# Filter.net
KiCad netlist of a schematic drawn in EAGLE
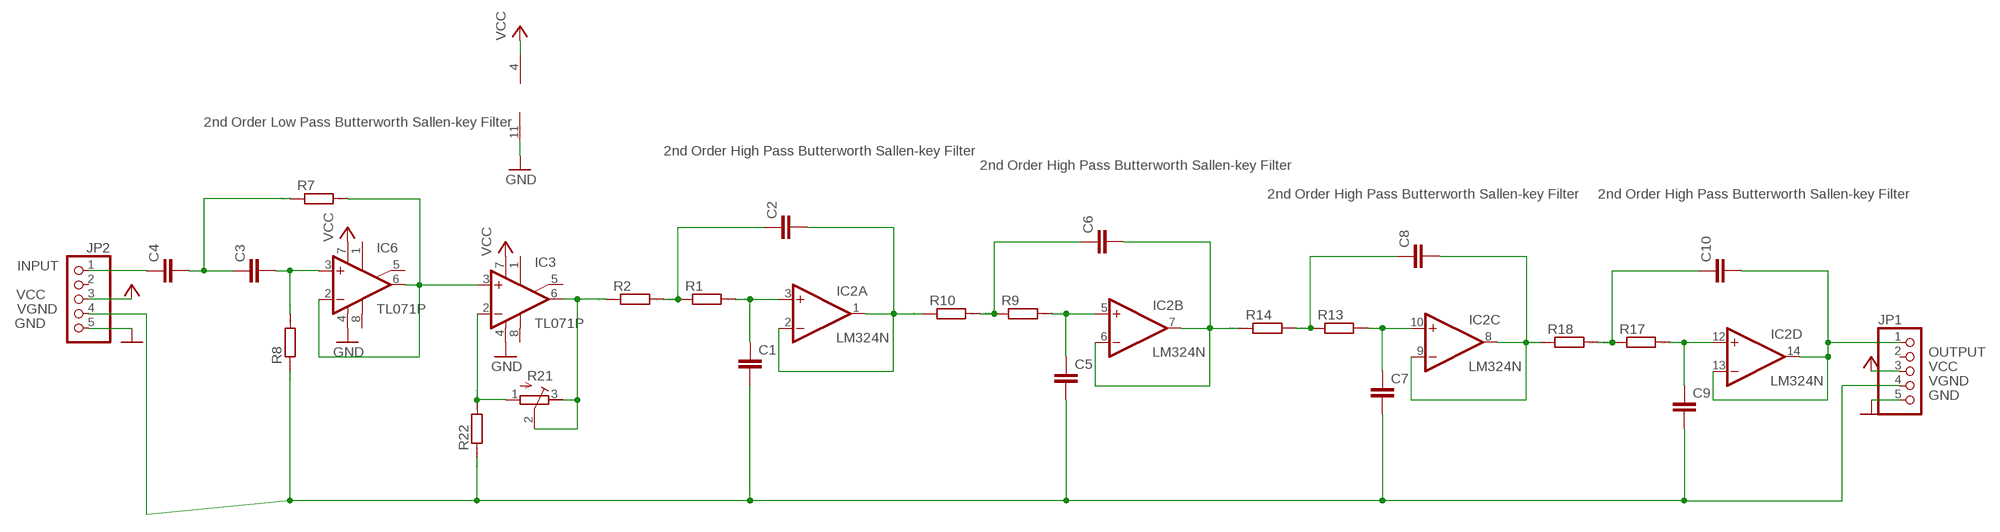
[diagram p0: schematic, sheet 1]

(export (version "E")
  (design (tool "Eeschema 10.0.6"))
  (components
    (comp (ref "C1")
      (value "C2.5/2")
      (footprint "eagle-import:C2.5-2")
      (libsource (lib "eagle-import") (part "C2.5/2"))
    )
    (comp (ref "C2")
      (value "C2.5/2")
      (footprint "eagle-import:C2.5-2")
      (libsource (lib "eagle-import") (part "C2.5/2"))
    )
    (comp (ref "C3")
      (value "C2.5/2")
      (footprint "eagle-import:C2.5-2")
      (libsource (lib "eagle-import") (part "C2.5/2"))
    )
    (comp (ref "C4")
      (value "C2.5/2")
      (footprint "eagle-import:C2.5-2")
      (libsource (lib "eagle-import") (part "C2.5/2"))
    )
    (comp (ref "C5")
      (value "C2.5/2")
      (footprint "eagle-import:C2.5-2")
      (libsource (lib "eagle-import") (part "C2.5/2"))
    )
    (comp (ref "C6")
      (value "C2.5/2")
      (footprint "eagle-import:C2.5-2")
      (libsource (lib "eagle-import") (part "C2.5/2"))
    )
    (comp (ref "C7")
      (value "C2.5/2")
      (footprint "eagle-import:C2.5-2")
      (libsource (lib "eagle-import") (part "C2.5/2"))
    )
    (comp (ref "C8")
      (value "C2.5/2")
      (footprint "eagle-import:C2.5-2")
      (libsource (lib "eagle-import") (part "C2.5/2"))
    )
    (comp (ref "C9")
      (value "C2.5/2")
      (footprint "eagle-import:C2.5-2")
      (libsource (lib "eagle-import") (part "C2.5/2"))
    )
    (comp (ref "C10")
      (value "C2.5/2")
      (footprint "eagle-import:C2.5-2")
      (libsource (lib "eagle-import") (part "C2.5/2"))
    )
    (comp (ref "IC2")
      (value "LM324N")
      (footprint "eagle-import:DIL14")
      (libsource (lib "eagle-import") (part "LM324N"))
    )
    (comp (ref "IC3")
      (value "TL071P")
      (footprint "eagle-import:DIL08")
      (libsource (lib "eagle-import") (part "TL071P"))
    )
    (comp (ref "IC6")
      (value "TL071P")
      (footprint "eagle-import:DIL08")
      (libsource (lib "eagle-import") (part "TL071P"))
    )
    (comp (ref "JP1")
      (value "PINHD-1X5")
      (footprint "eagle-import:1X05")
      (libsource (lib "eagle-import") (part "PINHD-1X5"))
    )
    (comp (ref "JP2")
      (value "PINHD-1X5")
      (footprint "eagle-import:1X05")
      (libsource (lib "eagle-import") (part "PINHD-1X5"))
    )
    (comp (ref "R1")
      (value "R0204/7")
      (footprint "eagle-import:0204_7")
      (libsource (lib "eagle-import") (part "R0204/7"))
    )
    (comp (ref "R2")
      (value "R0204/7")
      (footprint "eagle-import:0204_7")
      (libsource (lib "eagle-import") (part "R0204/7"))
    )
    (comp (ref "R7")
      (value "R0204/7")
      (footprint "eagle-import:0204_7")
      (libsource (lib "eagle-import") (part "R0204/7"))
    )
    (comp (ref "R8")
      (value "R0204/7")
      (footprint "eagle-import:0204_7")
      (libsource (lib "eagle-import") (part "R0204/7"))
    )
    (comp (ref "R9")
      (value "R0204/7")
      (footprint "eagle-import:0204_7")
      (libsource (lib "eagle-import") (part "R0204/7"))
    )
    (comp (ref "R10")
      (value "R0207/10")
      (footprint "eagle-import:0207_10")
      (libsource (lib "eagle-import") (part "R0207/10"))
    )
    (comp (ref "R13")
      (value "R0204/7")
      (footprint "eagle-import:0204_7")
      (libsource (lib "eagle-import") (part "R0204/7"))
    )
    (comp (ref "R14")
      (value "R0204/7")
      (footprint "eagle-import:0204_7")
      (libsource (lib "eagle-import") (part "R0204/7"))
    )
    (comp (ref "R17")
      (value "R0204/7")
      (footprint "eagle-import:0204_7")
      (libsource (lib "eagle-import") (part "R0204/7"))
    )
    (comp (ref "R18")
      (value "R0207/10")
      (footprint "eagle-import:0207_10")
      (libsource (lib "eagle-import") (part "R0207/10"))
    )
    (comp (ref "R21")
      (value "R-TRIMM3299W")
      (footprint "eagle-import:RTRIM3299W")
      (libsource (lib "eagle-import") (part "R-TRIMM3299W"))
    )
    (comp (ref "R22")
      (value "R0204/7")
      (footprint "eagle-import:0204_7")
      (libsource (lib "eagle-import") (part "R0204/7"))
    )
  )
  (nets
    (net (code "1") (name "/INPUT") (class "Default")
      (node (ref "C4") (pin "1") (pinfunction "1_1") (pintype "passive"))
      (node (ref "JP2") (pin "1") (pinfunction "1_1") (pintype "passive"))
    )
    (net (code "2") (name "/OUTPUT") (class "Default")
      (node (ref "C10") (pin "2") (pinfunction "2_2") (pintype "passive"))
      (node (ref "IC2") (pin "13") (pinfunction "-IN_13") (pintype "input"))
      (node (ref "IC2") (pin "14") (pinfunction "OUT_14") (pintype "output"))
      (node (ref "JP1") (pin "1") (pinfunction "1_1") (pintype "passive"))
    )
    (net (code "3") (name "/VGND") (class "Default")
      (node (ref "C1") (pin "2") (pinfunction "2_2") (pintype "passive"))
      (node (ref "C5") (pin "2") (pinfunction "2_2") (pintype "passive"))
      (node (ref "C7") (pin "2") (pinfunction "2_2") (pintype "passive"))
      (node (ref "C9") (pin "2") (pinfunction "2_2") (pintype "passive"))
      (node (ref "JP1") (pin "4") (pinfunction "4_4") (pintype "passive"))
      (node (ref "JP2") (pin "4") (pinfunction "4_4") (pintype "passive"))
      (node (ref "R22") (pin "1") (pinfunction "1_1") (pintype "passive"))
      (node (ref "R8") (pin "1") (pinfunction "1_1") (pintype "passive"))
    )
    (net (code "4") (name "GND") (class "Default")
      (node (ref "IC2") (pin "11") (pinfunction "V-_11") (pintype "power_in"))
      (node (ref "IC3") (pin "4") (pinfunction "V-_4") (pintype "power_in"))
      (node (ref "IC6") (pin "4") (pinfunction "V-_4") (pintype "power_in"))
      (node (ref "JP1") (pin "5") (pinfunction "5_5") (pintype "passive"))
      (node (ref "JP2") (pin "5") (pinfunction "5_5") (pintype "passive"))
    )
    (net (code "5") (name "Net-(C2-Pad1)") (class "Default")
      (node (ref "C2") (pin "1") (pinfunction "1_1") (pintype "passive"))
      (node (ref "R1") (pin "1") (pinfunction "1_1") (pintype "passive"))
      (node (ref "R2") (pin "2") (pinfunction "2_2") (pintype "passive"))
    )
    (net (code "6") (name "Net-(C3-Pad1)") (class "Default")
      (node (ref "C3") (pin "1") (pinfunction "1_1") (pintype "passive"))
      (node (ref "C4") (pin "2") (pinfunction "2_2") (pintype "passive"))
      (node (ref "R7") (pin "1") (pinfunction "1_1") (pintype "passive"))
    )
    (net (code "7") (name "Net-(C6-Pad1)") (class "Default")
      (node (ref "C6") (pin "1") (pinfunction "1_1") (pintype "passive"))
      (node (ref "R10") (pin "2") (pinfunction "2_2") (pintype "passive"))
      (node (ref "R9") (pin "1") (pinfunction "1_1") (pintype "passive"))
    )
    (net (code "8") (name "Net-(C8-Pad1)") (class "Default")
      (node (ref "C8") (pin "1") (pinfunction "1_1") (pintype "passive"))
      (node (ref "R13") (pin "1") (pinfunction "1_1") (pintype "passive"))
      (node (ref "R14") (pin "2") (pinfunction "2_2") (pintype "passive"))
    )
    (net (code "9") (name "Net-(C10-Pad1)") (class "Default")
      (node (ref "C10") (pin "1") (pinfunction "1_1") (pintype "passive"))
      (node (ref "R17") (pin "1") (pinfunction "1_1") (pintype "passive"))
      (node (ref "R18") (pin "2") (pinfunction "2_2") (pintype "passive"))
    )
    (net (code "10") (name "Net-(IC2A-+IN)") (class "Default")
      (node (ref "C1") (pin "1") (pinfunction "1_1") (pintype "passive"))
      (node (ref "IC2") (pin "3") (pinfunction "+IN_3") (pintype "input"))
      (node (ref "R1") (pin "2") (pinfunction "2_2") (pintype "passive"))
    )
    (net (code "11") (name "Net-(IC2A--IN)") (class "Default")
      (node (ref "C2") (pin "2") (pinfunction "2_2") (pintype "passive"))
      (node (ref "IC2") (pin "1") (pinfunction "OUT_1") (pintype "output"))
      (node (ref "IC2") (pin "2") (pinfunction "-IN_2") (pintype "input"))
      (node (ref "R10") (pin "1") (pinfunction "1_1") (pintype "passive"))
    )
    (net (code "12") (name "Net-(IC2B-+IN)") (class "Default")
      (node (ref "C5") (pin "1") (pinfunction "1_1") (pintype "passive"))
      (node (ref "IC2") (pin "5") (pinfunction "+IN_5") (pintype "input"))
      (node (ref "R9") (pin "2") (pinfunction "2_2") (pintype "passive"))
    )
    (net (code "13") (name "Net-(IC2B--IN)") (class "Default")
      (node (ref "C6") (pin "2") (pinfunction "2_2") (pintype "passive"))
      (node (ref "IC2") (pin "6") (pinfunction "-IN_6") (pintype "input"))
      (node (ref "IC2") (pin "7") (pinfunction "OUT_7") (pintype "output"))
      (node (ref "R14") (pin "1") (pinfunction "1_1") (pintype "passive"))
    )
    (net (code "14") (name "Net-(IC2C-+IN)") (class "Default")
      (node (ref "C7") (pin "1") (pinfunction "1_1") (pintype "passive"))
      (node (ref "IC2") (pin "10") (pinfunction "+IN_10") (pintype "input"))
      (node (ref "R13") (pin "2") (pinfunction "2_2") (pintype "passive"))
    )
    (net (code "15") (name "Net-(IC2C--IN)") (class "Default")
      (node (ref "C8") (pin "2") (pinfunction "2_2") (pintype "passive"))
      (node (ref "IC2") (pin "8") (pinfunction "OUT_8") (pintype "output"))
      (node (ref "IC2") (pin "9") (pinfunction "-IN_9") (pintype "input"))
      (node (ref "R18") (pin "1") (pinfunction "1_1") (pintype "passive"))
    )
    (net (code "16") (name "Net-(IC2D-+IN)") (class "Default")
      (node (ref "C9") (pin "1") (pinfunction "1_1") (pintype "passive"))
      (node (ref "IC2") (pin "12") (pinfunction "+IN_12") (pintype "input"))
      (node (ref "R17") (pin "2") (pinfunction "2_2") (pintype "passive"))
    )
    (net (code "17") (name "Net-(IC3-+IN)") (class "Default")
      (node (ref "IC3") (pin "3") (pinfunction "+IN_3") (pintype "input"))
      (node (ref "IC6") (pin "2") (pinfunction "-IN_2") (pintype "input"))
      (node (ref "IC6") (pin "6") (pinfunction "OUT_6") (pintype "output"))
      (node (ref "R7") (pin "2") (pinfunction "2_2") (pintype "passive"))
    )
    (net (code "18") (name "Net-(IC3--IN)") (class "Default")
      (node (ref "IC3") (pin "2") (pinfunction "-IN_2") (pintype "input"))
      (node (ref "R21") (pin "1") (pinfunction "A_1") (pintype "passive"))
      (node (ref "R22") (pin "2") (pinfunction "2_2") (pintype "passive"))
    )
    (net (code "19") (name "Net-(IC3-OUT)") (class "Default")
      (node (ref "IC3") (pin "6") (pinfunction "OUT_6") (pintype "output"))
      (node (ref "R2") (pin "1") (pinfunction "1_1") (pintype "passive"))
      (node (ref "R21") (pin "2") (pinfunction "S_2") (pintype "passive"))
      (node (ref "R21") (pin "3") (pinfunction "E_3") (pintype "passive"))
    )
    (net (code "20") (name "Net-(IC6-+IN)") (class "Default")
      (node (ref "C3") (pin "2") (pinfunction "2_2") (pintype "passive"))
      (node (ref "IC6") (pin "3") (pinfunction "+IN_3") (pintype "input"))
      (node (ref "R8") (pin "2") (pinfunction "2_2") (pintype "passive"))
    )
    (net (code "21") (name "VCC") (class "Default")
      (node (ref "IC2") (pin "4") (pinfunction "V+_4") (pintype "power_in"))
      (node (ref "IC3") (pin "7") (pinfunction "V+_7") (pintype "power_in"))
      (node (ref "IC6") (pin "7") (pinfunction "V+_7") (pintype "power_in"))
      (node (ref "JP1") (pin "3") (pinfunction "3_3") (pintype "passive"))
      (node (ref "JP2") (pin "3") (pinfunction "3_3") (pintype "passive"))
    )
    (net (code "22") (name "unconnected-(IC3-ON1-Pad1)") (class "Default")
      (node (ref "IC3") (pin "1") (pinfunction "ON1_1") (pintype "passive"))
    )
    (net (code "23") (name "unconnected-(IC3-ON2-Pad5)") (class "Default")
      (node (ref "IC3") (pin "5") (pinfunction "ON2_5") (pintype "passive"))
    )
    (net (code "24") (name "unconnected-(IC3-OPT-Pad8)") (class "Default")
      (node (ref "IC3") (pin "8") (pinfunction "OPT_8") (pintype "passive"))
    )
    (net (code "25") (name "unconnected-(IC6-ON1-Pad1)") (class "Default")
      (node (ref "IC6") (pin "1") (pinfunction "ON1_1") (pintype "passive"))
    )
    (net (code "26") (name "unconnected-(IC6-ON2-Pad5)") (class "Default")
      (node (ref "IC6") (pin "5") (pinfunction "ON2_5") (pintype "passive"))
    )
    (net (code "27") (name "unconnected-(IC6-OPT-Pad8)") (class "Default")
      (node (ref "IC6") (pin "8") (pinfunction "OPT_8") (pintype "passive"))
    )
    (net (code "28") (name "unconnected-(JP1-Pad2)") (class "Default")
      (node (ref "JP1") (pin "2") (pinfunction "2_2") (pintype "passive"))
    )
    (net (code "29") (name "unconnected-(JP2-Pad2)") (class "Default")
      (node (ref "JP2") (pin "2") (pinfunction "2_2") (pintype "passive"))
    )
  )
)
